# attiny_minimal.net
KiCad netlist of a schematic drawn in EAGLE
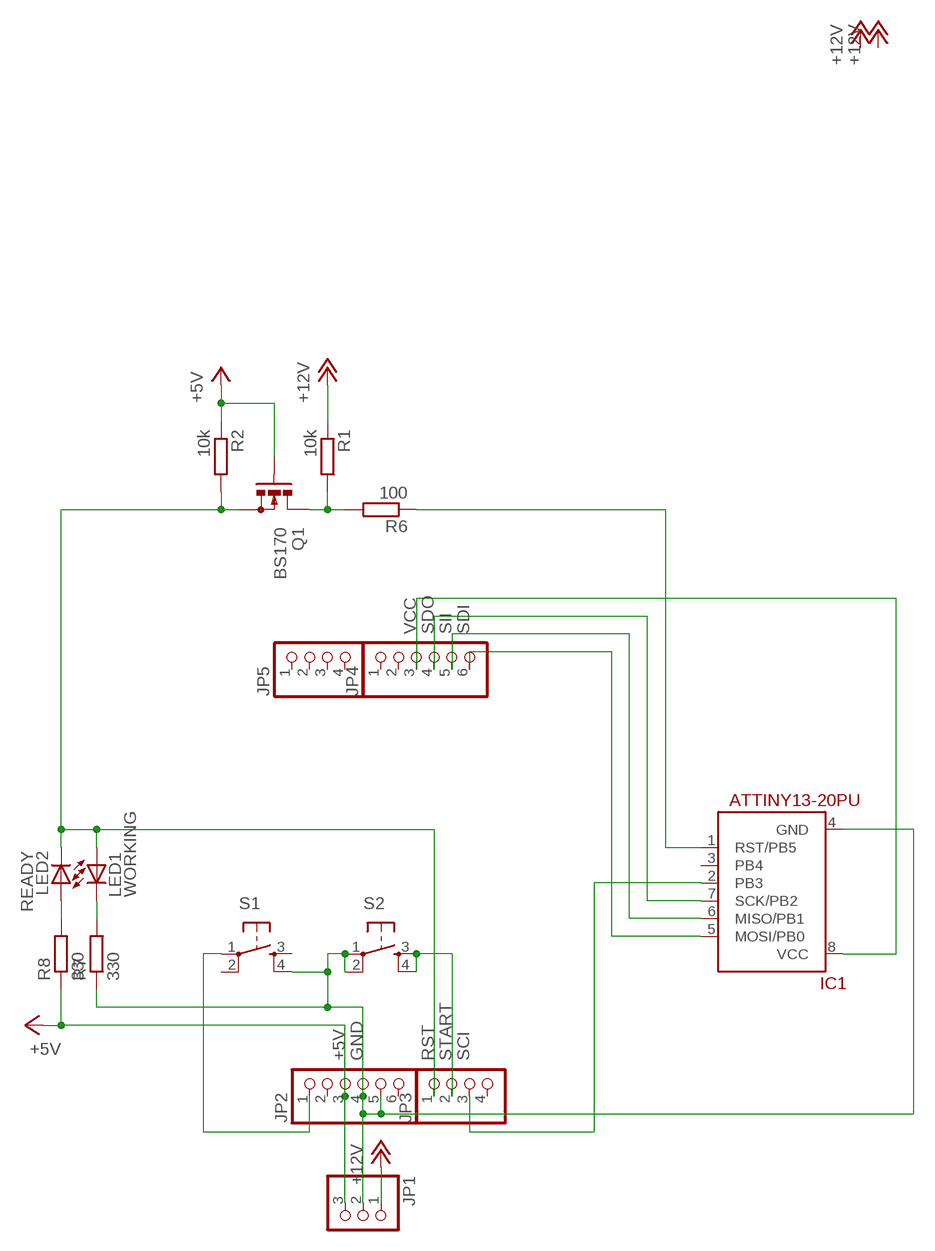
[diagram p0: schematic, sheet 1]

(export (version "E")
  (design (tool "Eeschema 10.0.6"))
  (components
    (comp (ref "IC1")
      (value "ATTINY13-20PU")
      (footprint "eagle-import:DIL08")
      (libsource (lib "eagle-import") (part "ATTINY13-20PU"))
    )
    (comp (ref "JP1")
      (value "PINHD-1X3/90")
      (footprint "eagle-import:1X03_90")
      (libsource (lib "eagle-import") (part "PINHD-1X3/90"))
    )
    (comp (ref "JP2")
      (value "PINHD-1X6")
      (footprint "eagle-import:1X06")
      (libsource (lib "eagle-import") (part "PINHD-1X6"))
    )
    (comp (ref "JP3")
      (value "PINHD-1X4")
      (footprint "eagle-import:1X04")
      (libsource (lib "eagle-import") (part "PINHD-1X4"))
    )
    (comp (ref "JP4")
      (value "PINHD-1X6")
      (footprint "eagle-import:1X06")
      (libsource (lib "eagle-import") (part "PINHD-1X6"))
    )
    (comp (ref "JP5")
      (value "PINHD-1X4")
      (footprint "eagle-import:1X04")
      (libsource (lib "eagle-import") (part "PINHD-1X4"))
    )
    (comp (ref "LED1")
      (value "WORKING")
      (footprint "eagle-import:LED3MM")
      (libsource (lib "eagle-import") (part "LED3MM"))
    )
    (comp (ref "LED2")
      (value "READY")
      (footprint "eagle-import:LED3MM")
      (libsource (lib "eagle-import") (part "LED3MM"))
    )
    (comp (ref "Q1")
      (value "BS170")
      (footprint "eagle-import:SOT54E")
      (libsource (lib "eagle-import") (part "BS170"))
    )
    (comp (ref "R1")
      (value "10k")
      (footprint "eagle-import:0207_2V")
      (libsource (lib "eagle-import") (part "R-EU_0207/2V"))
    )
    (comp (ref "R2")
      (value "10k")
      (footprint "eagle-import:0204_7")
      (libsource (lib "eagle-import") (part "R-EU_0204/7"))
    )
    (comp (ref "R6")
      (value "100")
      (footprint "eagle-import:0204_7")
      (libsource (lib "eagle-import") (part "R-EU_0204/7"))
    )
    (comp (ref "R7")
      (value "330")
      (footprint "eagle-import:0207_2V")
      (libsource (lib "eagle-import") (part "R-EU_0207/2V"))
    )
    (comp (ref "R8")
      (value "330")
      (footprint "eagle-import:0207_2V")
      (libsource (lib "eagle-import") (part "R-EU_0207/2V"))
    )
    (comp (ref "S1")
      (value "TAC_SWITCHPTH")
      (footprint "eagle-import:TACTILE-PTH")
      (libsource (lib "eagle-import") (part "TAC_SWITCHPTH"))
    )
    (comp (ref "S2")
      (value "TAC_SWITCHPTH")
      (footprint "eagle-import:TACTILE-PTH")
      (libsource (lib "eagle-import") (part "TAC_SWITCHPTH"))
    )
  )
  (nets
    (net (code "1") (name "+5V") (class "Default")
      (node (ref "JP1") (pin "3") (pinfunction "3_3") (pintype "passive"))
      (node (ref "JP2") (pin "3") (pinfunction "3_3") (pintype "passive"))
      (node (ref "Q1") (pin "G") (pinfunction "G_G") (pintype "passive"))
      (node (ref "R2") (pin "1") (pinfunction "1_1") (pintype "passive"))
      (node (ref "R8") (pin "1") (pinfunction "1_1") (pintype "passive"))
    )
    (net (code "2") (name "+12V") (class "Default")
      (node (ref "JP1") (pin "1") (pinfunction "1_1") (pintype "passive"))
      (node (ref "R1") (pin "1") (pinfunction "1_1") (pintype "passive"))
    )
    (net (code "3") (name "/GND") (class "Default")
      (node (ref "IC1") (pin "4") (pinfunction "GND_4") (pintype "power_in"))
      (node (ref "JP1") (pin "2") (pinfunction "2_2") (pintype "passive"))
      (node (ref "JP2") (pin "4") (pinfunction "4_4") (pintype "passive"))
      (node (ref "JP2") (pin "5") (pinfunction "5_5") (pintype "passive"))
      (node (ref "R7") (pin "1") (pinfunction "1_1") (pintype "passive"))
      (node (ref "S1") (pin "4") (pinfunction "4_4") (pintype "passive"))
      (node (ref "S2") (pin "1") (pinfunction "1_1") (pintype "passive"))
      (node (ref "S2") (pin "2") (pinfunction "2_2") (pintype "passive"))
    )
    (net (code "4") (name "/RST") (class "Default")
      (node (ref "JP3") (pin "1") (pinfunction "1_1") (pintype "passive"))
      (node (ref "LED1") (pin "A") (pinfunction "A_A") (pintype "passive"))
      (node (ref "LED2") (pin "K") (pinfunction "C_K") (pintype "passive"))
      (node (ref "Q1") (pin "S") (pinfunction "S_S") (pintype "passive"))
      (node (ref "R2") (pin "2") (pinfunction "2_2") (pintype "passive"))
    )
    (net (code "5") (name "/SCI") (class "Default")
      (node (ref "IC1") (pin "2") (pinfunction "PB3_2") (pintype "bidirectional"))
      (node (ref "JP3") (pin "3") (pinfunction "3_3") (pintype "passive"))
    )
    (net (code "6") (name "/SDI") (class "Default")
      (node (ref "IC1") (pin "5") (pinfunction "MOSI/PB0_5") (pintype "bidirectional"))
      (node (ref "JP4") (pin "6") (pinfunction "6_6") (pintype "passive"))
    )
    (net (code "7") (name "/SDO") (class "Default")
      (node (ref "IC1") (pin "7") (pinfunction "SCK/PB2_7") (pintype "bidirectional"))
      (node (ref "JP4") (pin "4") (pinfunction "4_4") (pintype "passive"))
    )
    (net (code "8") (name "/SII") (class "Default")
      (node (ref "IC1") (pin "6") (pinfunction "MISO/PB1_6") (pintype "bidirectional"))
      (node (ref "JP4") (pin "5") (pinfunction "5_5") (pintype "passive"))
    )
    (net (code "9") (name "/START") (class "Default")
      (node (ref "JP3") (pin "2") (pinfunction "2_2") (pintype "passive"))
      (node (ref "S2") (pin "3") (pinfunction "3_3") (pintype "passive"))
      (node (ref "S2") (pin "4") (pinfunction "4_4") (pintype "passive"))
    )
    (net (code "10") (name "/VCC") (class "Default")
      (node (ref "IC1") (pin "8") (pinfunction "VCC_8") (pintype "power_in"))
      (node (ref "JP4") (pin "3") (pinfunction "3_3") (pintype "passive"))
    )
    (net (code "11") (name "Net-(IC1-RST{slash}PB5)") (class "Default")
      (node (ref "IC1") (pin "1") (pinfunction "RST/PB5_1") (pintype "bidirectional"))
      (node (ref "R6") (pin "1") (pinfunction "1_1") (pintype "passive"))
    )
    (net (code "12") (name "Net-(JP2-Pad1)") (class "Default")
      (node (ref "JP2") (pin "1") (pinfunction "1_1") (pintype "passive"))
      (node (ref "S1") (pin "1") (pinfunction "1_1") (pintype "passive"))
    )
    (net (code "13") (name "Net-(LED1-C)") (class "Default")
      (node (ref "LED1") (pin "K") (pinfunction "C_K") (pintype "passive"))
      (node (ref "R7") (pin "2") (pinfunction "2_2") (pintype "passive"))
    )
    (net (code "14") (name "Net-(LED2-PadA)") (class "Default")
      (node (ref "LED2") (pin "A") (pinfunction "A_A") (pintype "passive"))
      (node (ref "R8") (pin "2") (pinfunction "2_2") (pintype "passive"))
    )
    (net (code "15") (name "Net-(Q1-PadD)") (class "Default")
      (node (ref "Q1") (pin "D") (pinfunction "D_D") (pintype "passive"))
      (node (ref "R1") (pin "2") (pinfunction "2_2") (pintype "passive"))
      (node (ref "R6") (pin "2") (pinfunction "2_2") (pintype "passive"))
    )
    (net (code "16") (name "unconnected-(IC1-PB4-Pad3)") (class "Default")
      (node (ref "IC1") (pin "3") (pinfunction "PB4_3") (pintype "bidirectional"))
    )
    (net (code "17") (name "unconnected-(JP2-Pad2)") (class "Default")
      (node (ref "JP2") (pin "2") (pinfunction "2_2") (pintype "passive"))
    )
    (net (code "18") (name "unconnected-(JP2-Pad6)") (class "Default")
      (node (ref "JP2") (pin "6") (pinfunction "6_6") (pintype "passive"))
    )
    (net (code "19") (name "unconnected-(JP3-Pad4)") (class "Default")
      (node (ref "JP3") (pin "4") (pinfunction "4_4") (pintype "passive"))
    )
    (net (code "20") (name "unconnected-(JP4-Pad1)") (class "Default")
      (node (ref "JP4") (pin "1") (pinfunction "1_1") (pintype "passive"))
    )
    (net (code "21") (name "unconnected-(JP4-Pad2)") (class "Default")
      (node (ref "JP4") (pin "2") (pinfunction "2_2") (pintype "passive"))
    )
    (net (code "22") (name "unconnected-(JP5-Pad1)") (class "Default")
      (node (ref "JP5") (pin "1") (pinfunction "1_1") (pintype "passive"))
    )
    (net (code "23") (name "unconnected-(JP5-Pad2)") (class "Default")
      (node (ref "JP5") (pin "2") (pinfunction "2_2") (pintype "passive"))
    )
    (net (code "24") (name "unconnected-(JP5-Pad3)") (class "Default")
      (node (ref "JP5") (pin "3") (pinfunction "3_3") (pintype "passive"))
    )
    (net (code "25") (name "unconnected-(JP5-Pad4)") (class "Default")
      (node (ref "JP5") (pin "4") (pinfunction "4_4") (pintype "passive"))
    )
    (net (code "26") (name "unconnected-(S1-Pad2)") (class "Default")
      (node (ref "S1") (pin "2") (pinfunction "2_2") (pintype "passive"))
    )
    (net (code "27") (name "unconnected-(S1-Pad3)") (class "Default")
      (node (ref "S1") (pin "3") (pinfunction "3_3") (pintype "passive"))
    )
  )
)
